# CurrentProbe.net
KiCad netlist of a schematic drawn in Altium Designer
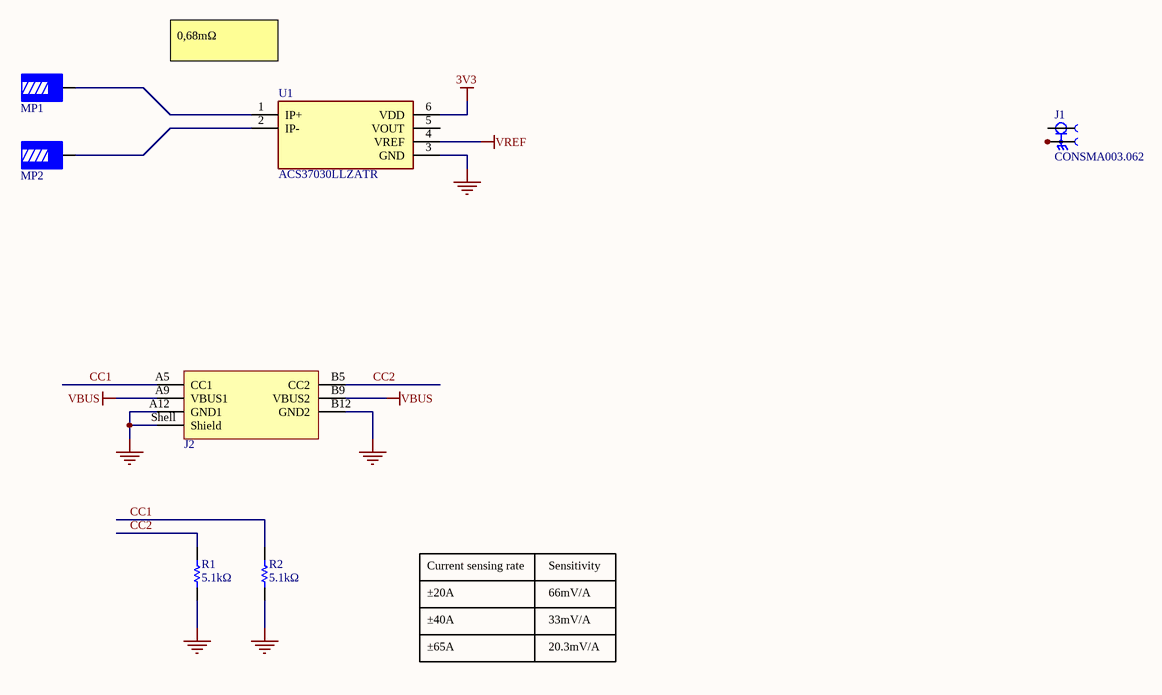
[diagram p0: CurrentProbe.SchDoc]

(export (version "E")
  (design (tool "Eeschema 10.0.6"))
  (components
    (comp (ref "J1")
      (value "CONSMA003.062")
      (footprint "CONSMA003.062")
      (description "SMA Connector Receptacle, Female Socket 50Ohm Board Edge, End Launch Solder")
      (fields (field (name "MF") "Linx Technologies"))
      (libsource (lib "MUAB_Altium_Lib") (part "CONSMA003.062"))
    )
    (comp (ref "J2")
      (value "632722100213")
      (footprint "632722100213")
      (description "WR-COM USB Power Delivery Type C Receptacle Horizontal SMT")
      (fields (field (name "MANUFACTURER") "Wurth Elektronik"))
      (libsource (lib "Altium_WR-USB (rev24c)") (part "632722100213"))
    )
    (comp (ref "MP1")
      (value "M3 x 5mm")
      (footprint "7461057_chemical surface")
      (description "WP-BUTR REDCUBE PRESS-FIT with internal thread, two-rows, L7W7H6mm, M3 x 5mm, 100A")
      (fields
        (field (name "MANUFACTURER PART NUMBER") "7461057")
        (field (name "MANUFACTURER") "Wurth Elektronik")
      )
      (libsource (lib "Altium_WP-BUTR (rev22b)") (part "7461057"))
    )
    (comp (ref "MP2")
      (value "M3 x 5mm")
      (footprint "7461057_chemical surface")
      (description "WP-BUTR REDCUBE PRESS-FIT with internal thread, two-rows, L7W7H6mm, M3 x 5mm, 100A")
      (fields
        (field (name "MANUFACTURER PART NUMBER") "7461057")
        (field (name "MANUFACTURER") "Wurth Elektronik")
      )
      (libsource (lib "Altium_WP-BUTR (rev22b)") (part "7461057"))
    )
    (comp (ref "R1")
      (value "RES")
      (footprint "RES_0603_H050 (_IPC_MD)")
      (description "5.1kΩ")
      (fields
        (field (name "PART NUMBER") "GPR06035K1")
        (field (name "R") "5.1kΩ")
        (field (name "TOLERANCE") "1")
      )
      (libsource (lib "EUROCircuits_Altium_lib") (part "RES"))
    )
    (comp (ref "R2")
      (value "RES")
      (footprint "RES_0603_H050 (_IPC_MD)")
      (description "5.1kΩ")
      (fields
        (field (name "PART NUMBER") "GPR06035K1")
        (field (name "R") "5.1kΩ")
        (field (name "TOLERANCE") "1")
      )
      (libsource (lib "EUROCircuits_Altium_lib") (part "RES"))
    )
    (comp (ref "U1")
      (value "ACS37030LLZATR")
      (footprint "SamacSys:ACS37030LLZATR020B3")
      (description "Current Sensor 40A 1 Channel Hall Effect Bidirectional 8-SOIC (0.154\", 3.90mm Width), 6 Leads")
      (fields
        (field (name "MANUFACTURER_PART_NUMBER") "ACS37030LLZATR-020B3")
        (field (name "MOUSER PART NUMBER") "250-ACS37030-020B3")
      )
      (libsource (lib "MUAB_Altium_Lib") (part "ACS37030LLZATR"))
    )
  )
  (nets
    (net (code "1") (name "/CC1") (class "Default")
      (node (ref "J2") (pin "A5") (pinfunction "CC1_A5") (pintype "passive"))
      (node (ref "R2") (pin "2") (pinfunction "2_2") (pintype "passive"))
    )
    (net (code "2") (name "/CC2") (class "Default")
      (node (ref "J2") (pin "B5") (pinfunction "CC2_B5") (pintype "passive"))
      (node (ref "R1") (pin "2") (pinfunction "2_2") (pintype "passive"))
    )
    (net (code "3") (name "3V3") (class "Default")
      (node (ref "U1") (pin "6") (pinfunction "VDD_6") (pintype "power_in"))
    )
    (net (code "4") (name "GND") (class "Default")
      (node (ref "J2") (pin "A12") (pinfunction "GND1_A12") (pintype "passive"))
      (node (ref "J2") (pin "B12") (pinfunction "GND2_B12") (pintype "passive"))
      (node (ref "J2") (pin "Shell") (pinfunction "Shield_Shell") (pintype "passive"))
      (node (ref "R1") (pin "1") (pinfunction "1_1") (pintype "passive"))
      (node (ref "R2") (pin "1") (pinfunction "1_1") (pintype "passive"))
      (node (ref "U1") (pin "3") (pinfunction "GND_3") (pintype "power_in"))
    )
    (net (code "5") (name "Net-(J1-2-PadS1)") (class "Default")
      (node (ref "J1") (pin "S1") (pinfunction "2_S1") (pintype "passive"))
      (node (ref "J1") (pin "S2") (pinfunction "2_S2") (pintype "passive"))
      (node (ref "J1") (pin "S3") (pinfunction "2_S3") (pintype "passive"))
      (node (ref "J1") (pin "S4") (pinfunction "2_S4") (pintype "passive"))
    )
    (net (code "6") (name "Net-(U1-IP+)") (class "Default")
      (node (ref "MP1") (pin "1") (pinfunction "1_1") (pintype "passive"))
      (node (ref "U1") (pin "1") (pinfunction "IP+_1") (pintype "passive"))
    )
    (net (code "7") (name "Net-(U1-IP-)") (class "Default")
      (node (ref "MP2") (pin "1") (pinfunction "1_1") (pintype "passive"))
      (node (ref "U1") (pin "2") (pinfunction "IP-_2") (pintype "passive"))
    )
    (net (code "8") (name "VBUS") (class "Default")
      (node (ref "J2") (pin "A9") (pinfunction "VBUS1_A9") (pintype "passive"))
      (node (ref "J2") (pin "B9") (pinfunction "VBUS2_B9") (pintype "passive"))
    )
    (net (code "9") (name "VREF") (class "Default")
      (node (ref "U1") (pin "4") (pinfunction "VREF_4") (pintype "passive"))
    )
    (net (code "10") (name "unconnected-(J1-Pad1)") (class "Default")
      (node (ref "J1") (pin "1") (pinfunction "1_1") (pintype "passive"))
    )
    (net (code "11") (name "unconnected-(U1-VOUT-Pad5)") (class "Default")
      (node (ref "U1") (pin "5") (pinfunction "VOUT_5") (pintype "passive"))
    )
  )
)
